# TLayerManager.net
KiCad netlist of a schematic drawn in Altium Designer
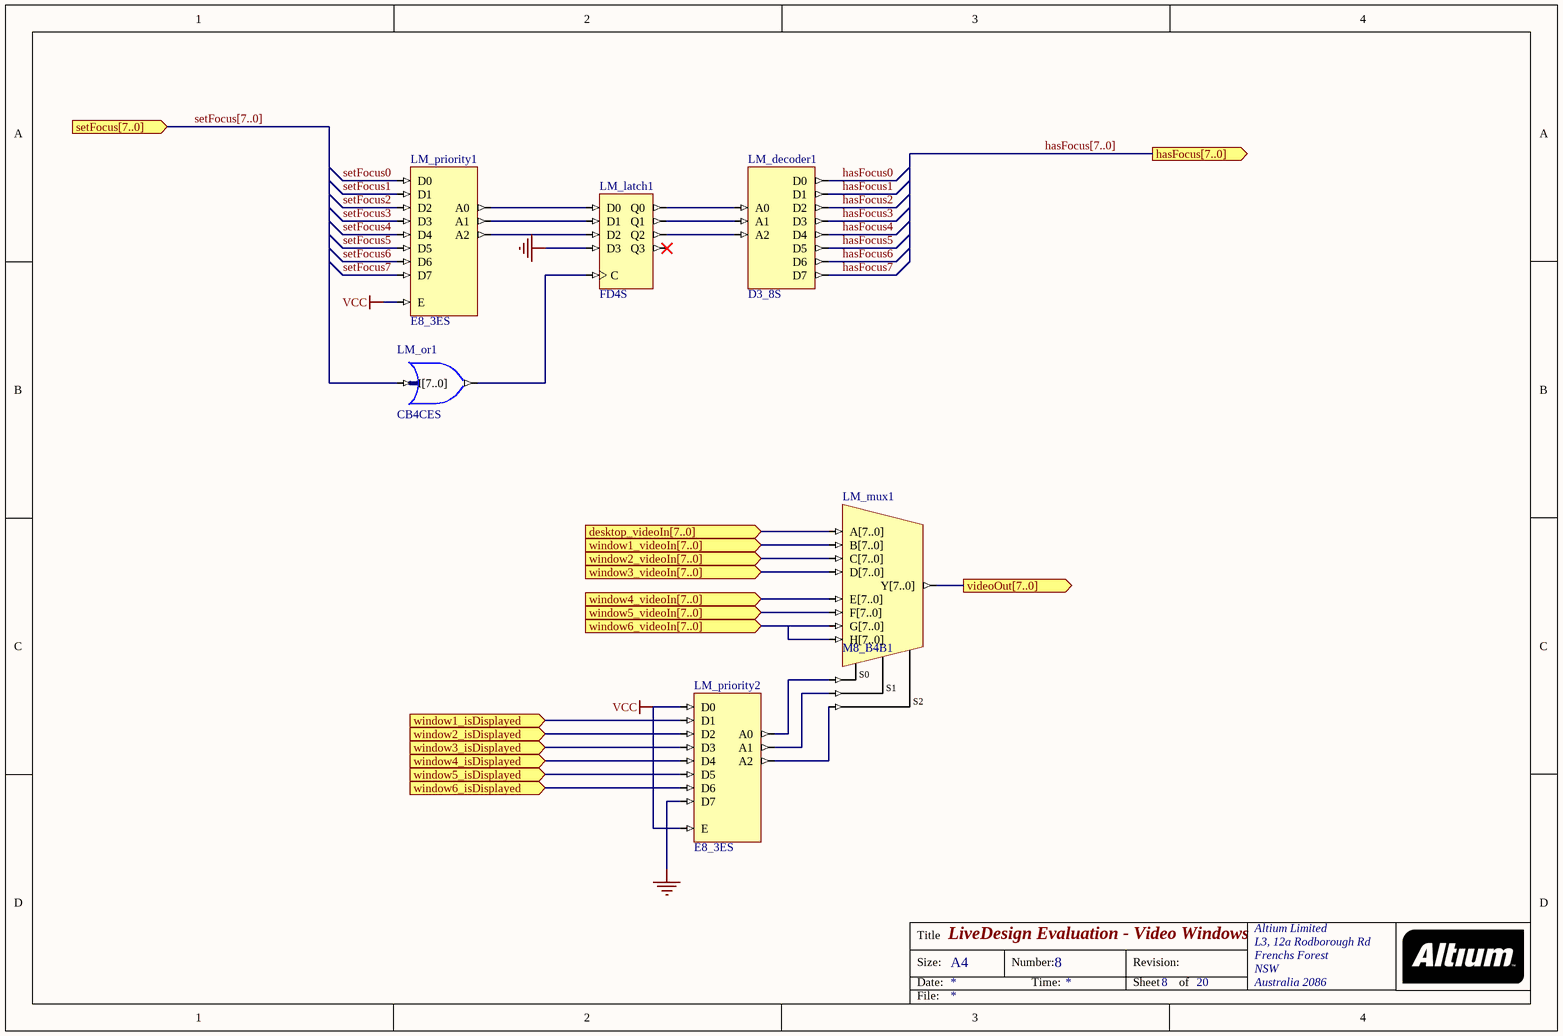
[diagram p0: TLayerManager.schDoc]

(export (version "E")
  (design (tool "Eeschema 10.0.6"))
  (components
    (comp (ref "LM_decoder1")
      (value "D3_8S")
      (description "Binary 3- to 8-Bit Decoder, Single Pin Version")
      (fields (field (name "PUBLISHER") "Altium Limited"))
      (libsource (lib "FPGA Generic") (part "D3_8S"))
    )
    (comp (ref "LM_latch1")
      (value "FD4S")
      (description "4-Bit D-Type Flip-Flop, Single Pin Version")
      (fields (field (name "PUBLISHER") "Altium Limited"))
      (libsource (lib "FPGA Generic") (part "FD4S"))
    )
    (comp (ref "LM_mux1")
      (value "M8_B4B1")
      (description "8x8-Bit Bus to 1x8-Bit Bus Multiplexer")
      (fields (field (name "PUBLISHER") "Altium Limited"))
      (libsource (lib "FPGA Generic") (part "M8_B8B1"))
    )
    (comp (ref "LM_or1")
      (value "CB4CES")
      (description "8-Input OR Gate, Bus Version")
      (fields (field (name "PUBLISHER") "Altium Limited"))
      (libsource (lib "FPGA Generic") (part "OR8B"))
    )
    (comp (ref "LM_priority1")
      (value "E8_3ES")
      (description "8- to 3-Bit Priority Encoder with Enable, Single Pin Version")
      (fields (field (name "PUBLISHER") "Altium Limited"))
      (libsource (lib "FPGA Generic") (part "E8_3ES"))
    )
    (comp (ref "LM_priority2")
      (value "E8_3ES")
      (description "8- to 3-Bit Priority Encoder with Enable, Single Pin Version")
      (fields (field (name "PUBLISHER") "Altium Limited"))
      (libsource (lib "FPGA Generic") (part "E8_3ES"))
    )
  )
  (nets
    (net (code "65") (name "/desktop_videoIn[7..0]") (class "Default")
      (node (ref "LM_mux1") (pin "A[7..0]") (pinfunction "A[7..0]_A[7..0]") (pintype "input"))
    )
    (net (code "66") (name "/hasFocus0") (class "Default")
      (node (ref "LM_decoder1") (pin "D0") (pinfunction "D0_D0") (pintype "output"))
    )
    (net (code "67") (name "/hasFocus1") (class "Default")
      (node (ref "LM_decoder1") (pin "D1") (pinfunction "D1_D1") (pintype "output"))
    )
    (net (code "68") (name "/hasFocus2") (class "Default")
      (node (ref "LM_decoder1") (pin "D2") (pinfunction "D2_D2") (pintype "output"))
    )
    (net (code "69") (name "/hasFocus3") (class "Default")
      (node (ref "LM_decoder1") (pin "D3") (pinfunction "D3_D3") (pintype "output"))
    )
    (net (code "70") (name "/hasFocus4") (class "Default")
      (node (ref "LM_decoder1") (pin "D4") (pinfunction "D4_D4") (pintype "output"))
    )
    (net (code "71") (name "/hasFocus5") (class "Default")
      (node (ref "LM_decoder1") (pin "D5") (pinfunction "D5_D5") (pintype "output"))
    )
    (net (code "72") (name "/hasFocus6") (class "Default")
      (node (ref "LM_decoder1") (pin "D6") (pinfunction "D6_D6") (pintype "output"))
    )
    (net (code "73") (name "/hasFocus7") (class "Default")
      (node (ref "LM_decoder1") (pin "D7") (pinfunction "D7_D7") (pintype "output"))
    )
    (net (code "75") (name "/setFocus0") (class "Default")
      (node (ref "LM_priority1") (pin "D0") (pinfunction "D0_D0") (pintype "input"))
    )
    (net (code "76") (name "/setFocus1") (class "Default")
      (node (ref "LM_priority1") (pin "D1") (pinfunction "D1_D1") (pintype "input"))
    )
    (net (code "77") (name "/setFocus2") (class "Default")
      (node (ref "LM_priority1") (pin "D2") (pinfunction "D2_D2") (pintype "input"))
    )
    (net (code "78") (name "/setFocus3") (class "Default")
      (node (ref "LM_priority1") (pin "D3") (pinfunction "D3_D3") (pintype "input"))
    )
    (net (code "79") (name "/setFocus4") (class "Default")
      (node (ref "LM_priority1") (pin "D4") (pinfunction "D4_D4") (pintype "input"))
    )
    (net (code "80") (name "/setFocus5") (class "Default")
      (node (ref "LM_priority1") (pin "D5") (pinfunction "D5_D5") (pintype "input"))
    )
    (net (code "81") (name "/setFocus6") (class "Default")
      (node (ref "LM_priority1") (pin "D6") (pinfunction "D6_D6") (pintype "input"))
    )
    (net (code "82") (name "/setFocus7") (class "Default")
      (node (ref "LM_priority1") (pin "D7") (pinfunction "D7_D7") (pintype "input"))
    )
    (net (code "83") (name "/setFocus[7..0]") (class "Default")
      (node (ref "LM_or1") (pin "I[7..0]") (pinfunction "I[7..0]_I[7..0]") (pintype "input"))
    )
    (net (code "84") (name "/videoOut[7..0]") (class "Default")
      (node (ref "LM_mux1") (pin "Y[7..0]") (pinfunction "Y[7..0]_Y[7..0]") (pintype "output"))
    )
    (net (code "85") (name "/window1_isDisplayed") (class "Default")
      (node (ref "LM_priority2") (pin "D1") (pinfunction "D1_D1") (pintype "input"))
    )
    (net (code "86") (name "/window1_videoIn[7..0]") (class "Default")
      (node (ref "LM_mux1") (pin "B[7..0]") (pinfunction "B[7..0]_B[7..0]") (pintype "input"))
    )
    (net (code "87") (name "/window2_isDisplayed") (class "Default")
      (node (ref "LM_priority2") (pin "D2") (pinfunction "D2_D2") (pintype "input"))
    )
    (net (code "88") (name "/window2_videoIn[7..0]") (class "Default")
      (node (ref "LM_mux1") (pin "C[7..0]") (pinfunction "C[7..0]_C[7..0]") (pintype "input"))
    )
    (net (code "89") (name "/window3_isDisplayed") (class "Default")
      (node (ref "LM_priority2") (pin "D3") (pinfunction "D3_D3") (pintype "input"))
    )
    (net (code "90") (name "/window3_videoIn[7..0]") (class "Default")
      (node (ref "LM_mux1") (pin "D[7..0]") (pinfunction "D[7..0]_D[7..0]") (pintype "input"))
    )
    (net (code "91") (name "/window4_isDisplayed") (class "Default")
      (node (ref "LM_priority2") (pin "D4") (pinfunction "D4_D4") (pintype "input"))
    )
    (net (code "92") (name "/window4_videoIn[7..0]") (class "Default")
      (node (ref "LM_mux1") (pin "E[7..0]") (pinfunction "E[7..0]_E[7..0]") (pintype "input"))
    )
    (net (code "93") (name "/window5_isDisplayed") (class "Default")
      (node (ref "LM_priority2") (pin "D5") (pinfunction "D5_D5") (pintype "input"))
    )
    (net (code "94") (name "/window5_videoIn[7..0]") (class "Default")
      (node (ref "LM_mux1") (pin "F[7..0]") (pinfunction "F[7..0]_F[7..0]") (pintype "input"))
    )
    (net (code "95") (name "/window6_isDisplayed") (class "Default")
      (node (ref "LM_priority2") (pin "D6") (pinfunction "D6_D6") (pintype "input"))
    )
    (net (code "96") (name "/window6_videoIn[7..0]") (class "Default")
      (node (ref "LM_mux1") (pin "G[7..0]") (pinfunction "G[7..0]_G[7..0]") (pintype "input"))
    )
    (net (code "97") (name "GND") (class "Default")
      (node (ref "LM_latch1") (pin "D3") (pinfunction "D3_D3") (pintype "input"))
      (node (ref "LM_priority2") (pin "D7") (pinfunction "D7_D7") (pintype "input"))
    )
    (net (code "98") (name "Net-(LM_decoder1-PadA0)") (class "Default")
      (node (ref "LM_decoder1") (pin "A0") (pinfunction "A0_A0") (pintype "input"))
      (node (ref "LM_latch1") (pin "Q0") (pinfunction "Q0_Q0") (pintype "output"))
    )
    (net (code "99") (name "Net-(LM_decoder1-PadA1)") (class "Default")
      (node (ref "LM_decoder1") (pin "A1") (pinfunction "A1_A1") (pintype "input"))
      (node (ref "LM_latch1") (pin "Q1") (pinfunction "Q1_Q1") (pintype "output"))
    )
    (net (code "100") (name "Net-(LM_decoder1-PadA2)") (class "Default")
      (node (ref "LM_decoder1") (pin "A2") (pinfunction "A2_A2") (pintype "input"))
      (node (ref "LM_latch1") (pin "Q2") (pinfunction "Q2_Q2") (pintype "output"))
    )
    (net (code "101") (name "Net-(LM_latch1-PadC)") (class "Default")
      (node (ref "LM_latch1") (pin "C") (pinfunction "C_C") (pintype "input"))
      (node (ref "LM_or1") (pin "O") (pinfunction "O_O") (pintype "output"))
    )
    (net (code "102") (name "Net-(LM_latch1-PadD0)") (class "Default")
      (node (ref "LM_latch1") (pin "D0") (pinfunction "D0_D0") (pintype "input"))
      (node (ref "LM_priority1") (pin "A0") (pinfunction "A0_A0") (pintype "output"))
    )
    (net (code "103") (name "Net-(LM_latch1-PadD1)") (class "Default")
      (node (ref "LM_latch1") (pin "D1") (pinfunction "D1_D1") (pintype "input"))
      (node (ref "LM_priority1") (pin "A1") (pinfunction "A1_A1") (pintype "output"))
    )
    (net (code "104") (name "Net-(LM_latch1-PadD2)") (class "Default")
      (node (ref "LM_latch1") (pin "D2") (pinfunction "D2_D2") (pintype "input"))
      (node (ref "LM_priority1") (pin "A2") (pinfunction "A2_A2") (pintype "output"))
    )
    (net (code "105") (name "Net-(LM_mux1-PadS0)") (class "Default")
      (node (ref "LM_mux1") (pin "S0") (pinfunction "S0_S0") (pintype "input"))
      (node (ref "LM_priority2") (pin "A0") (pinfunction "A0_A0") (pintype "output"))
    )
    (net (code "106") (name "Net-(LM_mux1-PadS1)") (class "Default")
      (node (ref "LM_mux1") (pin "S1") (pinfunction "S1_S1") (pintype "input"))
      (node (ref "LM_priority2") (pin "A1") (pinfunction "A1_A1") (pintype "output"))
    )
    (net (code "107") (name "Net-(LM_mux1-PadS2)") (class "Default")
      (node (ref "LM_mux1") (pin "S2") (pinfunction "S2_S2") (pintype "input"))
      (node (ref "LM_priority2") (pin "A2") (pinfunction "A2_A2") (pintype "output"))
    )
    (net (code "108") (name "VCC") (class "Default")
      (node (ref "LM_priority1") (pin "E") (pinfunction "E_E") (pintype "input"))
      (node (ref "LM_priority2") (pin "D0") (pinfunction "D0_D0") (pintype "input"))
      (node (ref "LM_priority2") (pin "E") (pinfunction "E_E") (pintype "input"))
    )
    (net (code "109") (name "unconnected-(LM_latch1-PadQ3)") (class "Default")
      (node (ref "LM_latch1") (pin "Q3") (pinfunction "Q3_Q3") (pintype "output+no_connect"))
    )
    (net (code "110") (name "unconnected-(LM_mux1-PadH[7..0])") (class "Default")
      (node (ref "LM_mux1") (pin "H[7..0]") (pinfunction "H[7..0]_H[7..0]") (pintype "input"))
    )
  )
)
